# PSprogramboard.net
KiCad netlist of a schematic drawn in EAGLE
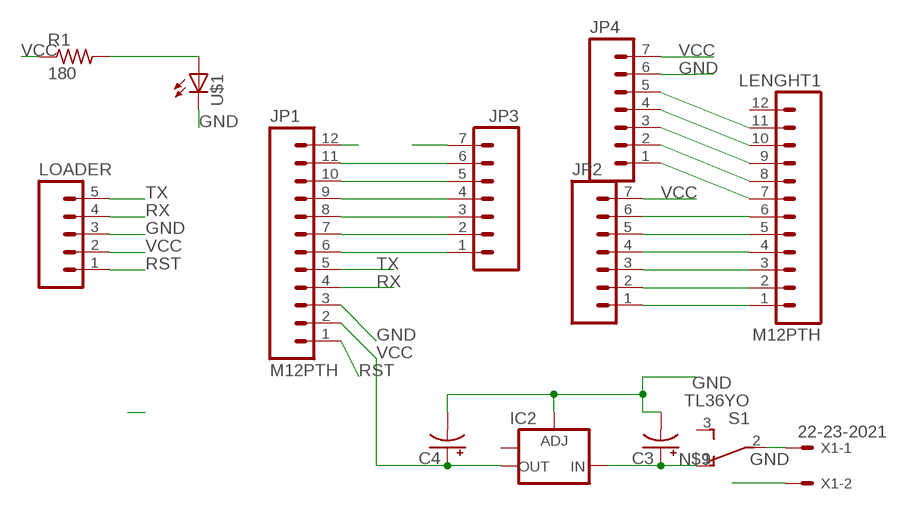
[diagram p0: schematic, sheet 1]

(export (version "E")
  (design (tool "Eeschema 10.0.6"))
  (components
    (comp (ref "C3")
      (value "CAP_POLC")
      (footprint "eagle-import:PANASONIC_C")
      (libsource (lib "eagle-import") (part "CAP_POLC"))
    )
    (comp (ref "C4")
      (value "CAP_POLC")
      (footprint "eagle-import:PANASONIC_C")
      (libsource (lib "eagle-import") (part "CAP_POLC"))
    )
    (comp (ref "IC2")
      (value "V_REG_LM1117SOT223")
      (footprint "eagle-import:SOT223")
      (libsource (lib "eagle-import") (part "V_REG_LM1117SOT223"))
    )
    (comp (ref "JP1")
      (value "M12PTH")
      (footprint "eagle-import:1X12")
      (libsource (lib "eagle-import") (part "M12PTH"))
    )
    (comp (ref "JP2")
      (value "M07")
      (footprint "eagle-import:1X07")
      (libsource (lib "eagle-import") (part "M07"))
    )
    (comp (ref "JP3")
      (value "M07")
      (footprint "eagle-import:1X07")
      (libsource (lib "eagle-import") (part "M07"))
    )
    (comp (ref "JP4")
      (value "M07")
      (footprint "eagle-import:1X07")
      (libsource (lib "eagle-import") (part "M07"))
    )
    (comp (ref "LENGHT1")
      (value "M12PTH")
      (footprint "eagle-import:1X12")
      (libsource (lib "eagle-import") (part "M12PTH"))
    )
    (comp (ref "LOADER")
      (value "M05PTH")
      (footprint "eagle-import:1X05")
      (libsource (lib "eagle-import") (part "M05PTH"))
    )
    (comp (ref "R1")
      (value "180")
      (footprint "eagle-import:1206")
      (libsource (lib "eagle-import") (part "RESISTOR1206"))
    )
    (comp (ref "S1")
      (value "TL36YO")
      (footprint "eagle-import:TL3XYO")
      (libsource (lib "eagle-import") (part "TL36YO"))
    )
    (comp (ref "U$1")
      (value "LED1206")
      (footprint "eagle-import:1206")
      (libsource (lib "eagle-import") (part "LED1206"))
    )
    (comp (ref "X1")
      (value "22-23-2021")
      (footprint "eagle-import:22-23-2021")
      (fields (field (name "MF") "MOLEX"))
      (libsource (lib "eagle-import") (part "22-23-2021"))
    )
  )
  (nets
    (net (code "1") (name "/GND") (class "Default")
      (node (ref "C3") (pin "-") (pinfunction "-_-") (pintype "passive"))
      (node (ref "C4") (pin "-") (pinfunction "-_-") (pintype "passive"))
      (node (ref "IC2") (pin "1") (pinfunction "ADJ_1") (pintype "input"))
      (node (ref "JP1") (pin "11") (pinfunction "11_11") (pintype "passive"))
      (node (ref "JP1") (pin "12") (pinfunction "12_12") (pintype "passive"))
      (node (ref "JP1") (pin "3") (pinfunction "3_3") (pintype "passive"))
      (node (ref "JP2") (pin "6") (pinfunction "6_6") (pintype "passive"))
      (node (ref "JP3") (pin "6") (pinfunction "6_6") (pintype "passive"))
      (node (ref "JP4") (pin "6") (pinfunction "6_6") (pintype "passive"))
      (node (ref "LENGHT1") (pin "6") (pinfunction "6_6") (pintype "passive"))
      (node (ref "LOADER") (pin "3") (pinfunction "3_3") (pintype "passive"))
      (node (ref "U$1") (pin "2") (pinfunction "C_2") (pintype "passive"))
      (node (ref "X1") (pin "2") (pinfunction "S_2") (pintype "passive"))
    )
    (net (code "2") (name "/N$9") (class "Default")
      (node (ref "C3") (pin "+") (pinfunction "+_+") (pintype "passive"))
      (node (ref "IC2") (pin "3") (pinfunction "IN_3") (pintype "input"))
      (node (ref "S1") (pin "1") (pinfunction "O_1") (pintype "passive"))
    )
    (net (code "3") (name "/RST") (class "Default")
      (node (ref "JP1") (pin "1") (pinfunction "1_1") (pintype "passive"))
      (node (ref "LOADER") (pin "1") (pinfunction "1_1") (pintype "passive"))
    )
    (net (code "4") (name "/RX") (class "Default")
      (node (ref "JP1") (pin "4") (pinfunction "4_4") (pintype "passive"))
      (node (ref "LOADER") (pin "4") (pinfunction "4_4") (pintype "passive"))
    )
    (net (code "5") (name "/TX") (class "Default")
      (node (ref "JP1") (pin "5") (pinfunction "5_5") (pintype "passive"))
      (node (ref "LOADER") (pin "5") (pinfunction "5_5") (pintype "passive"))
    )
    (net (code "6") (name "/VCC") (class "Default")
      (node (ref "C4") (pin "+") (pinfunction "+_+") (pintype "passive"))
      (node (ref "IC2") (pin "2") (pinfunction "OUT_2") (pintype "output"))
      (node (ref "JP1") (pin "2") (pinfunction "2_2") (pintype "passive"))
      (node (ref "JP2") (pin "7") (pinfunction "7_7") (pintype "passive"))
      (node (ref "JP3") (pin "7") (pinfunction "7_7") (pintype "passive"))
      (node (ref "JP4") (pin "7") (pinfunction "7_7") (pintype "passive"))
      (node (ref "LOADER") (pin "2") (pinfunction "2_2") (pintype "passive"))
      (node (ref "R1") (pin "1") (pinfunction "1_1") (pintype "passive"))
    )
    (net (code "7") (name "Net-(JP1-Pad6)") (class "Default")
      (node (ref "JP1") (pin "6") (pinfunction "6_6") (pintype "passive"))
      (node (ref "JP3") (pin "1") (pinfunction "1_1") (pintype "passive"))
    )
    (net (code "8") (name "Net-(JP1-Pad7)") (class "Default")
      (node (ref "JP1") (pin "7") (pinfunction "7_7") (pintype "passive"))
      (node (ref "JP3") (pin "2") (pinfunction "2_2") (pintype "passive"))
    )
    (net (code "9") (name "Net-(JP1-Pad8)") (class "Default")
      (node (ref "JP1") (pin "8") (pinfunction "8_8") (pintype "passive"))
      (node (ref "JP3") (pin "3") (pinfunction "3_3") (pintype "passive"))
    )
    (net (code "10") (name "Net-(JP1-Pad9)") (class "Default")
      (node (ref "JP1") (pin "9") (pinfunction "9_9") (pintype "passive"))
      (node (ref "JP3") (pin "4") (pinfunction "4_4") (pintype "passive"))
    )
    (net (code "11") (name "Net-(JP1-Pad10)") (class "Default")
      (node (ref "JP1") (pin "10") (pinfunction "10_10") (pintype "passive"))
      (node (ref "JP3") (pin "5") (pinfunction "5_5") (pintype "passive"))
    )
    (net (code "12") (name "Net-(JP2-Pad1)") (class "Default")
      (node (ref "JP2") (pin "1") (pinfunction "1_1") (pintype "passive"))
      (node (ref "LENGHT1") (pin "1") (pinfunction "1_1") (pintype "passive"))
    )
    (net (code "13") (name "Net-(JP2-Pad2)") (class "Default")
      (node (ref "JP2") (pin "2") (pinfunction "2_2") (pintype "passive"))
      (node (ref "LENGHT1") (pin "2") (pinfunction "2_2") (pintype "passive"))
    )
    (net (code "14") (name "Net-(JP2-Pad3)") (class "Default")
      (node (ref "JP2") (pin "3") (pinfunction "3_3") (pintype "passive"))
      (node (ref "LENGHT1") (pin "3") (pinfunction "3_3") (pintype "passive"))
    )
    (net (code "15") (name "Net-(JP2-Pad4)") (class "Default")
      (node (ref "JP2") (pin "4") (pinfunction "4_4") (pintype "passive"))
      (node (ref "LENGHT1") (pin "4") (pinfunction "4_4") (pintype "passive"))
    )
    (net (code "16") (name "Net-(JP2-Pad5)") (class "Default")
      (node (ref "JP2") (pin "5") (pinfunction "5_5") (pintype "passive"))
      (node (ref "LENGHT1") (pin "5") (pinfunction "5_5") (pintype "passive"))
    )
    (net (code "17") (name "Net-(JP4-Pad1)") (class "Default")
      (node (ref "JP4") (pin "1") (pinfunction "1_1") (pintype "passive"))
      (node (ref "LENGHT1") (pin "7") (pinfunction "7_7") (pintype "passive"))
    )
    (net (code "18") (name "Net-(JP4-Pad2)") (class "Default")
      (node (ref "JP4") (pin "2") (pinfunction "2_2") (pintype "passive"))
      (node (ref "LENGHT1") (pin "8") (pinfunction "8_8") (pintype "passive"))
    )
    (net (code "19") (name "Net-(JP4-Pad3)") (class "Default")
      (node (ref "JP4") (pin "3") (pinfunction "3_3") (pintype "passive"))
      (node (ref "LENGHT1") (pin "9") (pinfunction "9_9") (pintype "passive"))
    )
    (net (code "20") (name "Net-(JP4-Pad4)") (class "Default")
      (node (ref "JP4") (pin "4") (pinfunction "4_4") (pintype "passive"))
      (node (ref "LENGHT1") (pin "10") (pinfunction "10_10") (pintype "passive"))
    )
    (net (code "21") (name "Net-(JP4-Pad5)") (class "Default")
      (node (ref "JP4") (pin "5") (pinfunction "5_5") (pintype "passive"))
      (node (ref "LENGHT1") (pin "11") (pinfunction "11_11") (pintype "passive"))
    )
    (net (code "22") (name "Net-(S1-P)") (class "Default")
      (node (ref "S1") (pin "2") (pinfunction "P_2") (pintype "passive"))
      (node (ref "X1") (pin "1") (pinfunction "S_1") (pintype "passive"))
    )
    (net (code "23") (name "Net-(U$1-A)") (class "Default")
      (node (ref "R1") (pin "2") (pinfunction "2_2") (pintype "passive"))
      (node (ref "U$1") (pin "1") (pinfunction "A_1") (pintype "passive"))
    )
    (net (code "24") (name "unconnected-(IC2-OUT-Pad4)") (class "Default")
      (node (ref "IC2") (pin "4") (pinfunction "OUT_4") (pintype "output"))
    )
    (net (code "25") (name "unconnected-(LENGHT1-Pad12)") (class "Default")
      (node (ref "LENGHT1") (pin "12") (pinfunction "12_12") (pintype "passive"))
    )
    (net (code "26") (name "unconnected-(S1-S-Pad3)") (class "Default")
      (node (ref "S1") (pin "3") (pinfunction "S_3") (pintype "passive"))
    )
  )
)
